# SD-101D_Robotics_Cape.net
KiCad netlist of a schematic drawn in EAGLE
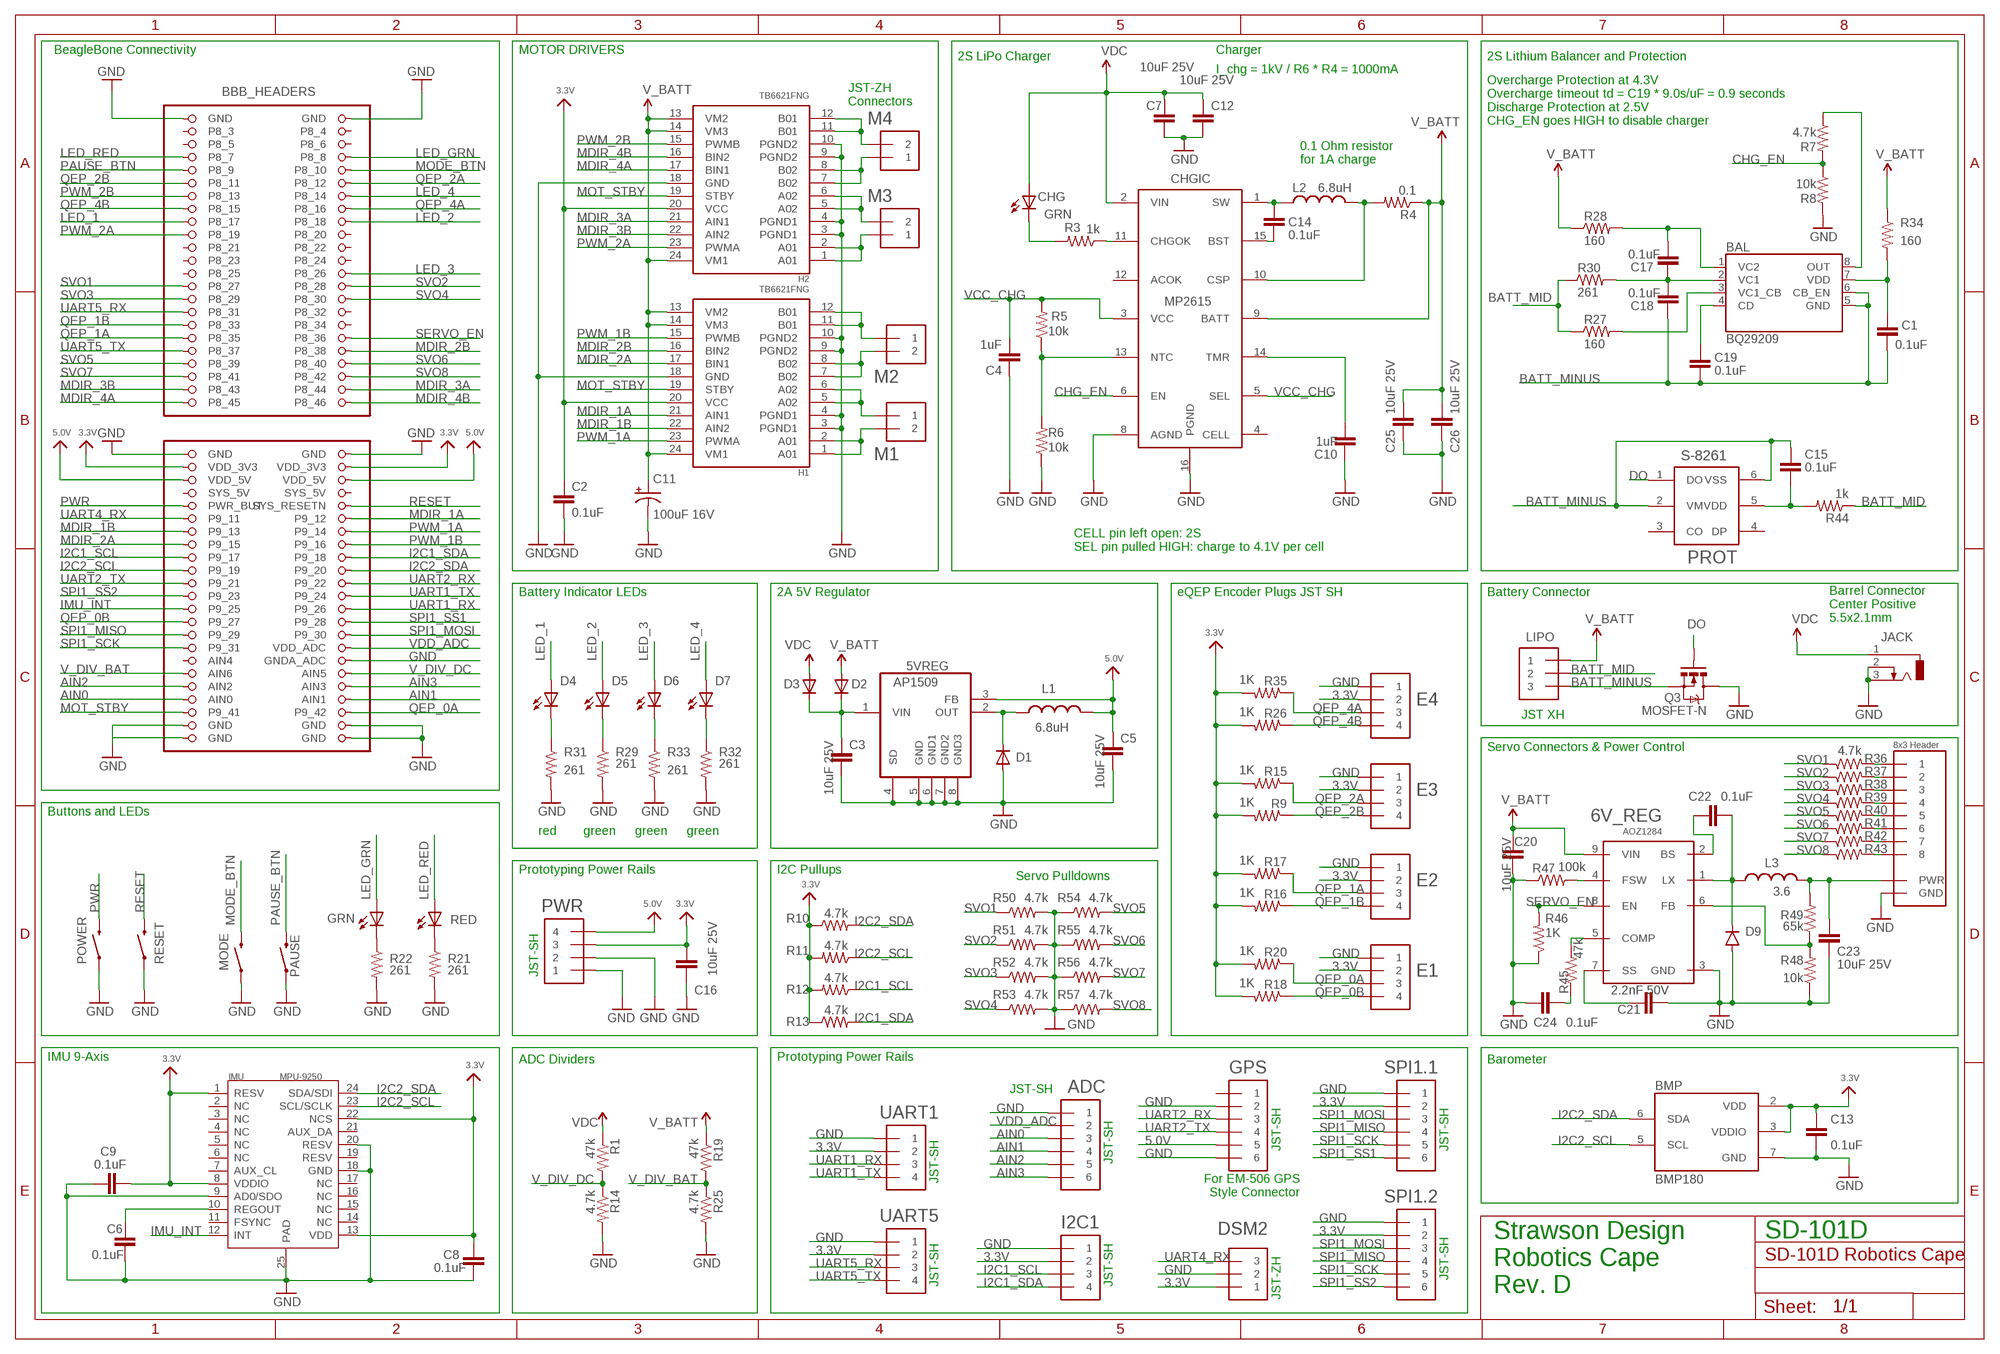
[diagram p0: schematic, sheet 1]

(export (version "E")
  (design (tool "Eeschema 10.0.6"))
  (components
    (comp (ref "5VREG")
      (value "AP1509SOIC-8-TIGHT")
      (footprint "eagle-import:SO08-TIGHT")
      (libsource (lib "eagle-import") (part "AP1509SOIC-8-TIGHT"))
    )
    (comp (ref "6V_REG")
      (value "AOZ1284")
      (footprint "eagle-import:SO08-EXPOSED")
      (libsource (lib "eagle-import") (part "AOZ1284"))
    )
    (comp (ref "ADC")
      (value "JST_SH_6")
      (footprint "eagle-import:JST_SH_6")
      (libsource (lib "eagle-import") (part "JST_SH_6"))
    )
    (comp (ref "BAL")
      (value "BQ29209")
      (footprint "eagle-import:8-SON_3X3MM")
      (libsource (lib "eagle-import") (part "BQ29209"))
    )
    (comp (ref "BBB_HEADERS")
      (value "BEAGLEBONE_OUTLINE")
      (footprint "eagle-import:BEAGLEBONE_SHIELD")
      (libsource (lib "eagle-import") (part "BEAGLEBONE_OUTLINE"))
    )
    (comp (ref "BMP")
      (value "BMP180")
      (footprint "eagle-import:BMP180")
      (libsource (lib "eagle-import") (part "BMP180"))
    )
    (comp (ref "C1")
      (value "0.1uF")
      (footprint "eagle-import:0402-CAP")
      (libsource (lib "eagle-import") (part "Strawson_Eagle_Lib_CAP0402-CAP"))
    )
    (comp (ref "C2")
      (value "0.1uF")
      (footprint "eagle-import:0402-CAP")
      (libsource (lib "eagle-import") (part "Strawson_Eagle_Lib_CAP0402-CAP"))
    )
    (comp (ref "C3")
      (value "10uF 25V")
      (footprint "eagle-import:0805")
      (libsource (lib "eagle-import") (part "CAP0805"))
    )
    (comp (ref "C4")
      (value "1uF")
      (footprint "eagle-import:0402-CAP")
      (libsource (lib "eagle-import") (part "Strawson_Eagle_Lib_CAP0402-CAP"))
    )
    (comp (ref "C5")
      (value "10uF 25V")
      (footprint "eagle-import:0805")
      (libsource (lib "eagle-import") (part "CAP0805"))
    )
    (comp (ref "C6")
      (value "0.1uF")
      (footprint "eagle-import:0402-CAP")
      (libsource (lib "eagle-import") (part "Strawson_Eagle_Lib_CAP0402-CAP"))
    )
    (comp (ref "C7")
      (value "10uF 25V")
      (footprint "eagle-import:0805")
      (libsource (lib "eagle-import") (part "CAP0805"))
    )
    (comp (ref "C8")
      (value "0.1uF")
      (footprint "eagle-import:0402-CAP")
      (libsource (lib "eagle-import") (part "Strawson_Eagle_Lib_CAP0402-CAP"))
    )
    (comp (ref "C9")
      (value "0.1uF")
      (footprint "eagle-import:0402-CAP")
      (libsource (lib "eagle-import") (part "Strawson_Eagle_Lib_CAP0402-CAP"))
    )
    (comp (ref "C10")
      (value "1uF")
      (footprint "eagle-import:0402-CAP")
      (libsource (lib "eagle-import") (part "Strawson_Eagle_Lib_CAP0402-CAP"))
    )
    (comp (ref "C11")
      (value "100uF 16V")
      (footprint "eagle-import:PANASONIC_D")
      (libsource (lib "eagle-import") (part "CPOL-USD"))
    )
    (comp (ref "C12")
      (value "10uF 25V")
      (footprint "eagle-import:0805")
      (libsource (lib "eagle-import") (part "CAP0805"))
    )
    (comp (ref "C13")
      (value "0.1uF")
      (footprint "eagle-import:0402-CAP")
      (libsource (lib "eagle-import") (part "Strawson_Eagle_Lib_CAP0402-CAP"))
    )
    (comp (ref "C14")
      (value "0.1uF")
      (footprint "eagle-import:0402-CAP")
      (libsource (lib "eagle-import") (part "Strawson_Eagle_Lib_CAP0402-CAP"))
    )
    (comp (ref "C15")
      (value "0.1uF")
      (footprint "eagle-import:0402-CAP")
      (libsource (lib "eagle-import") (part "Strawson_Eagle_Lib_CAP0402-CAP"))
    )
    (comp (ref "C16")
      (value "10uF 25V")
      (footprint "eagle-import:0805")
      (libsource (lib "eagle-import") (part "CAP0805"))
    )
    (comp (ref "C17")
      (value "0.1uF")
      (footprint "eagle-import:0402-CAP")
      (libsource (lib "eagle-import") (part "Strawson_Eagle_Lib_CAP0402-CAP"))
    )
    (comp (ref "C18")
      (value "0.1uF")
      (footprint "eagle-import:0402-CAP")
      (libsource (lib "eagle-import") (part "Strawson_Eagle_Lib_CAP0402-CAP"))
    )
    (comp (ref "C19")
      (value "0.1uF")
      (footprint "eagle-import:0402-CAP")
      (libsource (lib "eagle-import") (part "Strawson_Eagle_Lib_CAP0402-CAP"))
    )
    (comp (ref "C20")
      (value "10uF 25V")
      (footprint "eagle-import:0805")
      (libsource (lib "eagle-import") (part "CAP0805"))
    )
    (comp (ref "C21")
      (value "2.2nF 50V")
      (footprint "eagle-import:0402-CAP")
      (libsource (lib "eagle-import") (part "Strawson_Eagle_Lib_CAP0402-CAP"))
    )
    (comp (ref "C22")
      (value "0.1uF")
      (footprint "eagle-import:0402-CAP")
      (libsource (lib "eagle-import") (part "Strawson_Eagle_Lib_CAP0402-CAP"))
    )
    (comp (ref "C23")
      (value "10uF 25V")
      (footprint "eagle-import:0805")
      (libsource (lib "eagle-import") (part "CAP0805"))
    )
    (comp (ref "C24")
      (value "0.1uF")
      (footprint "eagle-import:0402-CAP")
      (libsource (lib "eagle-import") (part "Strawson_Eagle_Lib_CAP0402-CAP"))
    )
    (comp (ref "C25")
      (value "10uF 25V")
      (footprint "eagle-import:0805")
      (libsource (lib "eagle-import") (part "CAP0805"))
    )
    (comp (ref "C26")
      (value "10uF 25V")
      (footprint "eagle-import:0805")
      (libsource (lib "eagle-import") (part "CAP0805"))
    )
    (comp (ref "CHG")
      (value "GRN")
      (footprint "eagle-import:LED-0603")
      (libsource (lib "eagle-import") (part "LED0603"))
    )
    (comp (ref "CHGIC")
      (value "MP2615")
      (footprint "eagle-import:MP2615")
      (libsource (lib "eagle-import") (part "MP2615"))
    )
    (comp (ref "D1")
      (value "DIODESOD-123")
      (footprint "eagle-import:SOD-123")
      (libsource (lib "eagle-import") (part "DIODESOD-123"))
    )
    (comp (ref "D2")
      (value "DIODESOD-123")
      (footprint "eagle-import:SOD-123")
      (libsource (lib "eagle-import") (part "DIODESOD-123"))
    )
    (comp (ref "D3")
      (value "DIODESOD-123")
      (footprint "eagle-import:SOD-123")
      (libsource (lib "eagle-import") (part "DIODESOD-123"))
    )
    (comp (ref "D4")
      (value "RED")
      (footprint "eagle-import:LED-0603")
      (libsource (lib "eagle-import") (part "LED0603"))
    )
    (comp (ref "D5")
      (value "GREEN")
      (footprint "eagle-import:LED-0603")
      (libsource (lib "eagle-import") (part "LED0603"))
    )
    (comp (ref "D6")
      (value "GREEN")
      (footprint "eagle-import:LED-0603")
      (libsource (lib "eagle-import") (part "LED0603"))
    )
    (comp (ref "D7")
      (value "GREEN")
      (footprint "eagle-import:LED-0603")
      (libsource (lib "eagle-import") (part "LED0603"))
    )
    (comp (ref "D9")
      (value "DIODEDO214AA")
      (footprint "eagle-import:DO-214AA")
      (libsource (lib "eagle-import") (part "DIODEDO214AA"))
    )
    (comp (ref "DSM2")
      (value "JST_ZH_3")
      (footprint "eagle-import:JST_ZH_3")
      (libsource (lib "eagle-import") (part "JST_ZH_3"))
    )
    (comp (ref "E1")
      (value "JST_SH_4")
      (footprint "eagle-import:JST_SH_4_SMD")
      (libsource (lib "eagle-import") (part "JST_SH_4"))
    )
    (comp (ref "E2")
      (value "JST_SH_4")
      (footprint "eagle-import:JST_SH_4_SMD")
      (libsource (lib "eagle-import") (part "JST_SH_4"))
    )
    (comp (ref "E3")
      (value "JST_SH_4")
      (footprint "eagle-import:JST_SH_4_SMD")
      (libsource (lib "eagle-import") (part "JST_SH_4"))
    )
    (comp (ref "E4")
      (value "JST_SH_4")
      (footprint "eagle-import:JST_SH_4_SMD")
      (libsource (lib "eagle-import") (part "JST_SH_4"))
    )
    (comp (ref "GPS")
      (value "JST_SH_6")
      (footprint "eagle-import:JST_SH_6")
      (libsource (lib "eagle-import") (part "JST_SH_6"))
    )
    (comp (ref "GRN")
      (value "GRN")
      (footprint "eagle-import:LED-0603")
      (libsource (lib "eagle-import") (part "LED0603"))
    )
    (comp (ref "H1")
      (value "TB6621FNG")
      (footprint "eagle-import:SSOP24")
      (libsource (lib "eagle-import") (part "TB6621FNG"))
    )
    (comp (ref "H2")
      (value "TB6621FNG")
      (footprint "eagle-import:SSOP24")
      (libsource (lib "eagle-import") (part "TB6621FNG"))
    )
    (comp (ref "I2C1")
      (value "JST_SH_4")
      (footprint "eagle-import:JST_SH_4_SMD")
      (libsource (lib "eagle-import") (part "JST_SH_4"))
    )
    (comp (ref "IMU")
      (value "MPU-9250")
      (footprint "eagle-import:QFN24G-0.4-3X3MM")
      (libsource (lib "eagle-import") (part "MPU-9250"))
    )
    (comp (ref "JACK")
      (value "5.5x2.1mm")
      (footprint "eagle-import:DCJ0303")
      (libsource (lib "eagle-import") (part "DCJ0303"))
    )
    (comp (ref "L1")
      (value "6.8uH")
      (footprint "eagle-import:SRN6045")
      (libsource (lib "eagle-import") (part "INDUCTORBOURNS_SRN6045"))
    )
    (comp (ref "L2")
      (value "6.8uH")
      (footprint "eagle-import:SRN6045")
      (libsource (lib "eagle-import") (part "INDUCTORBOURNS_SRN6045"))
    )
    (comp (ref "L3")
      (value "3.6")
      (footprint "eagle-import:8X8MM_INDUCTOR")
      (libsource (lib "eagle-import") (part "INDUCTOR"))
    )
    (comp (ref "LIPO")
      (value "JST_XH_3-PIN")
      (footprint "eagle-import:JST_XH_3-PIN")
      (libsource (lib "eagle-import") (part "JST_XH_3-PIN"))
    )
    (comp (ref "M1")
      (value "JST_ZH_2")
      (footprint "eagle-import:JST_ZH_2")
      (libsource (lib "eagle-import") (part "JST_ZH_2"))
    )
    (comp (ref "M2")
      (value "JST_ZH_2")
      (footprint "eagle-import:JST_ZH_2")
      (libsource (lib "eagle-import") (part "JST_ZH_2"))
    )
    (comp (ref "M3")
      (value "JST_ZH_2")
      (footprint "eagle-import:JST_ZH_2")
      (libsource (lib "eagle-import") (part "JST_ZH_2"))
    )
    (comp (ref "M4")
      (value "JST_ZH_2")
      (footprint "eagle-import:JST_ZH_2")
      (libsource (lib "eagle-import") (part "JST_ZH_2"))
    )
    (comp (ref "MODE")
      (value "SWITCH-MOMENTARY-2-SMD-1101NE")
      (footprint "eagle-import:TACTILE-SWITCH-1101NE")
      (libsource (lib "eagle-import") (part "SWITCH-MOMENTARY-2-SMD-1101NE"))
    )
    (comp (ref "PAUSE")
      (value "SWITCH-MOMENTARY-2-SMD-1101NE")
      (footprint "eagle-import:TACTILE-SWITCH-1101NE")
      (libsource (lib "eagle-import") (part "SWITCH-MOMENTARY-2-SMD-1101NE"))
    )
    (comp (ref "POWER")
      (value "SWITCH-MOMENTARY-2-SMD-1101NE")
      (footprint "eagle-import:TACTILE-SWITCH-1101NE")
      (libsource (lib "eagle-import") (part "SWITCH-MOMENTARY-2-SMD-1101NE"))
    )
    (comp (ref "PROT")
      (value "S-8261")
      (footprint "eagle-import:SOT-236")
      (libsource (lib "eagle-import") (part "S-8261"))
    )
    (comp (ref "PWR")
      (value "JST_SH_4")
      (footprint "eagle-import:JST_SH_4_SMD")
      (libsource (lib "eagle-import") (part "JST_SH_4"))
    )
    (comp (ref "Q3")
      (value "MOSFET-N")
      (footprint "eagle-import:SO08-TIGHT")
      (libsource (lib "eagle-import") (part "MOSFET-NCHANNEL"))
    )
    (comp (ref "R1")
      (value "47k")
      (footprint "eagle-import:0402-RES")
      (libsource (lib "eagle-import") (part "RESISTOR0402-RES"))
    )
    (comp (ref "R3")
      (value "1k")
      (footprint "eagle-import:0402-RES")
      (libsource (lib "eagle-import") (part "RESISTOR0402-RES"))
    )
    (comp (ref "R4")
      (value "0.1")
      (footprint "eagle-import:0603-RES")
      (libsource (lib "eagle-import") (part "RESISTOR0603"))
    )
    (comp (ref "R5")
      (value "10k")
      (footprint "eagle-import:0402-RES")
      (libsource (lib "eagle-import") (part "RESISTOR0402-RES"))
    )
    (comp (ref "R6")
      (value "10k")
      (footprint "eagle-import:0402-RES")
      (libsource (lib "eagle-import") (part "RESISTOR0402-RES"))
    )
    (comp (ref "R7")
      (value "4.7k")
      (footprint "eagle-import:0402-RES")
      (libsource (lib "eagle-import") (part "RESISTOR0402-RES"))
    )
    (comp (ref "R8")
      (value "10k")
      (footprint "eagle-import:0402-RES")
      (libsource (lib "eagle-import") (part "RESISTOR0402-RES"))
    )
    (comp (ref "R9")
      (value "1K")
      (footprint "eagle-import:0402-RES")
      (libsource (lib "eagle-import") (part "RESISTOR0402-RES"))
    )
    (comp (ref "R10")
      (value "4.7k")
      (footprint "eagle-import:0402-RES")
      (libsource (lib "eagle-import") (part "RESISTOR0402-RES"))
    )
    (comp (ref "R11")
      (value "4.7k")
      (footprint "eagle-import:0402-RES")
      (libsource (lib "eagle-import") (part "RESISTOR0402-RES"))
    )
    (comp (ref "R12")
      (value "4.7k")
      (footprint "eagle-import:0402-RES")
      (libsource (lib "eagle-import") (part "RESISTOR0402-RES"))
    )
    (comp (ref "R13")
      (value "4.7k")
      (footprint "eagle-import:0402-RES")
      (libsource (lib "eagle-import") (part "RESISTOR0402-RES"))
    )
    (comp (ref "R14")
      (value "4.7k")
      (footprint "eagle-import:0402-RES")
      (libsource (lib "eagle-import") (part "RESISTOR0402-RES"))
    )
    (comp (ref "R15")
      (value "1K")
      (footprint "eagle-import:0402-RES")
      (libsource (lib "eagle-import") (part "RESISTOR0402-RES"))
    )
    (comp (ref "R16")
      (value "1K")
      (footprint "eagle-import:0402-RES")
      (libsource (lib "eagle-import") (part "RESISTOR0402-RES"))
    )
    (comp (ref "R17")
      (value "1K")
      (footprint "eagle-import:0402-RES")
      (libsource (lib "eagle-import") (part "RESISTOR0402-RES"))
    )
    (comp (ref "R18")
      (value "1K")
      (footprint "eagle-import:0402-RES")
      (libsource (lib "eagle-import") (part "RESISTOR0402-RES"))
    )
    (comp (ref "R19")
      (value "47k")
      (footprint "eagle-import:0402-RES")
      (libsource (lib "eagle-import") (part "RESISTOR0402-RES"))
    )
    (comp (ref "R20")
      (value "1K")
      (footprint "eagle-import:0402-RES")
      (libsource (lib "eagle-import") (part "RESISTOR0402-RES"))
    )
    (comp (ref "R21")
      (value "261")
      (footprint "eagle-import:0402-RES")
      (libsource (lib "eagle-import") (part "RESISTOR0402-RES"))
    )
    (comp (ref "R22")
      (value "261")
      (footprint "eagle-import:0402-RES")
      (libsource (lib "eagle-import") (part "RESISTOR0402-RES"))
    )
    (comp (ref "R25")
      (value "4.7k")
      (footprint "eagle-import:0402-RES")
      (libsource (lib "eagle-import") (part "RESISTOR0402-RES"))
    )
    (comp (ref "R26")
      (value "1K")
      (footprint "eagle-import:0402-RES")
      (libsource (lib "eagle-import") (part "RESISTOR0402-RES"))
    )
    (comp (ref "R27")
      (value "160")
      (footprint "eagle-import:0402-RES")
      (libsource (lib "eagle-import") (part "RESISTOR0402-RES"))
    )
    (comp (ref "R28")
      (value "160")
      (footprint "eagle-import:0402-RES")
      (libsource (lib "eagle-import") (part "RESISTOR0402-RES"))
    )
    (comp (ref "R29")
      (value "261")
      (footprint "eagle-import:0402-RES")
      (libsource (lib "eagle-import") (part "RESISTOR0402-RES"))
    )
    (comp (ref "R30")
      (value "261")
      (footprint "eagle-import:0402-RES")
      (libsource (lib "eagle-import") (part "RESISTOR0402-RES"))
    )
    (comp (ref "R31")
      (value "261")
      (footprint "eagle-import:0402-RES")
      (libsource (lib "eagle-import") (part "RESISTOR0402-RES"))
    )
    (comp (ref "R32")
      (value "261")
      (footprint "eagle-import:0402-RES")
      (libsource (lib "eagle-import") (part "RESISTOR0402-RES"))
    )
    (comp (ref "R33")
      (value "261")
      (footprint "eagle-import:0402-RES")
      (libsource (lib "eagle-import") (part "RESISTOR0402-RES"))
    )
    (comp (ref "R34")
      (value "160")
      (footprint "eagle-import:0402-RES")
      (libsource (lib "eagle-import") (part "RESISTOR0402-RES"))
    )
    (comp (ref "R35")
      (value "1K")
      (footprint "eagle-import:0402-RES")
      (libsource (lib "eagle-import") (part "RESISTOR0402-RES"))
    )
    (comp (ref "R36")
      (value "4.7k")
      (footprint "eagle-import:0402-RES")
      (libsource (lib "eagle-import") (part "RESISTOR0402-RES"))
    )
    (comp (ref "R37")
      (value "4.7k")
      (footprint "eagle-import:0402-RES")
      (libsource (lib "eagle-import") (part "RESISTOR0402-RES"))
    )
    (comp (ref "R38")
      (value "4.7k")
      (footprint "eagle-import:0402-RES")
      (libsource (lib "eagle-import") (part "RESISTOR0402-RES"))
    )
    (comp (ref "R39")
      (value "4.7k")
      (footprint "eagle-import:0402-RES")
      (libsource (lib "eagle-import") (part "RESISTOR0402-RES"))
    )
    (comp (ref "R40")
      (value "4.7k")
      (footprint "eagle-import:0402-RES")
      (libsource (lib "eagle-import") (part "RESISTOR0402-RES"))
    )
    (comp (ref "R41")
      (value "4.7k")
      (footprint "eagle-import:0402-RES")
      (libsource (lib "eagle-import") (part "RESISTOR0402-RES"))
    )
    (comp (ref "R42")
      (value "4.7k")
      (footprint "eagle-import:0402-RES")
      (libsource (lib "eagle-import") (part "RESISTOR0402-RES"))
    )
    (comp (ref "R43")
      (value "4.7k")
      (footprint "eagle-import:0402-RES")
      (libsource (lib "eagle-import") (part "RESISTOR0402-RES"))
    )
    (comp (ref "R44")
      (value "1k")
      (footprint "eagle-import:0402-RES")
      (libsource (lib "eagle-import") (part "RESISTOR0402-RES"))
    )
    (comp (ref "R45")
      (value "47k")
      (footprint "eagle-import:0402-RES")
      (libsource (lib "eagle-import") (part "RESISTOR0402-RES"))
    )
    (comp (ref "R46")
      (value "1K")
      (footprint "eagle-import:0402-RES")
      (libsource (lib "eagle-import") (part "RESISTOR0402-RES"))
    )
    (comp (ref "R47")
      (value "100k")
      (footprint "eagle-import:0402-RES")
      (libsource (lib "eagle-import") (part "RESISTOR0402-RES"))
    )
    (comp (ref "R48")
      (value "10k")
      (footprint "eagle-import:0402-RES")
      (libsource (lib "eagle-import") (part "RESISTOR0402-RES"))
    )
    (comp (ref "R49")
      (value "65k")
      (footprint "eagle-import:0402-RES")
      (libsource (lib "eagle-import") (part "RESISTOR0402-RES"))
    )
    (comp (ref "R50")
      (value "4.7k")
      (footprint "eagle-import:0402-RES")
      (libsource (lib "eagle-import") (part "RESISTOR0402-RES"))
    )
    (comp (ref "R51")
      (value "4.7k")
      (footprint "eagle-import:0402-RES")
      (libsource (lib "eagle-import") (part "RESISTOR0402-RES"))
    )
    (comp (ref "R52")
      (value "4.7k")
      (footprint "eagle-import:0402-RES")
      (libsource (lib "eagle-import") (part "RESISTOR0402-RES"))
    )
    (comp (ref "R53")
      (value "4.7k")
      (footprint "eagle-import:0402-RES")
      (libsource (lib "eagle-import") (part "RESISTOR0402-RES"))
    )
    (comp (ref "R54")
      (value "4.7k")
      (footprint "eagle-import:0402-RES")
      (libsource (lib "eagle-import") (part "RESISTOR0402-RES"))
    )
    (comp (ref "R55")
      (value "4.7k")
      (footprint "eagle-import:0402-RES")
      (libsource (lib "eagle-import") (part "RESISTOR0402-RES"))
    )
    (comp (ref "R56")
      (value "4.7k")
      (footprint "eagle-import:0402-RES")
      (libsource (lib "eagle-import") (part "RESISTOR0402-RES"))
    )
    (comp (ref "R57")
      (value "4.7k")
      (footprint "eagle-import:0402-RES")
      (libsource (lib "eagle-import") (part "RESISTOR0402-RES"))
    )
    (comp (ref "RED")
      (value "RED")
      (footprint "eagle-import:LED-0603")
      (libsource (lib "eagle-import") (part "LED0603"))
    )
    (comp (ref "RESET")
      (value "SWITCH-MOMENTARY-2-SMD-1101NE")
      (footprint "eagle-import:TACTILE-SWITCH-1101NE")
      (libsource (lib "eagle-import") (part "SWITCH-MOMENTARY-2-SMD-1101NE"))
    )
    (comp (ref "SPI1.1")
      (value "JST_SH_6")
      (footprint "eagle-import:JST_SH_6")
      (libsource (lib "eagle-import") (part "JST_SH_6"))
    )
    (comp (ref "SPI1.2")
      (value "JST_SH_6")
      (footprint "eagle-import:JST_SH_6")
      (libsource (lib "eagle-import") (part "JST_SH_6"))
    )
    (comp (ref "U$1")
      (value "SERVO_HEADERS_8X")
      (footprint "eagle-import:3X8_0.1__HEADER")
      (libsource (lib "eagle-import") (part "SERVO_HEADERS_8X"))
    )
    (comp (ref "UART1")
      (value "JST_SH_4")
      (footprint "eagle-import:JST_SH_4_SMD")
      (libsource (lib "eagle-import") (part "JST_SH_4"))
    )
    (comp (ref "UART5")
      (value "JST_SH_4")
      (footprint "eagle-import:JST_SH_4_SMD")
      (libsource (lib "eagle-import") (part "JST_SH_4"))
    )
  )
  (nets
    (net (code "1") (name "/AIN0") (class "Default")
      (node (ref "ADC") (pin "3") (pinfunction "3_3") (pintype "bidirectional"))
      (node (ref "BBB_HEADERS") (pin "85") (pinfunction "AIN0_85") (pintype "power_in"))
    )
    (net (code "2") (name "/AIN1") (class "Default")
      (node (ref "ADC") (pin "4") (pinfunction "4_4") (pintype "bidirectional"))
      (node (ref "BBB_HEADERS") (pin "86") (pinfunction "AIN1_86") (pintype "passive"))
    )
    (net (code "3") (name "/AIN2") (class "Default")
      (node (ref "ADC") (pin "5") (pinfunction "5_5") (pintype "bidirectional"))
      (node (ref "BBB_HEADERS") (pin "83") (pinfunction "AIN2_83") (pintype "passive"))
    )
    (net (code "4") (name "/AIN3") (class "Default")
      (node (ref "ADC") (pin "6") (pinfunction "6_6") (pintype "bidirectional"))
      (node (ref "BBB_HEADERS") (pin "84") (pinfunction "AIN3_84") (pintype "passive"))
    )
    (net (code "5") (name "/BATT_MID") (class "Default")
      (node (ref "LIPO") (pin "P$2") (pinfunction "2_P$2") (pintype "passive"))
      (node (ref "R27") (pin "1") (pinfunction "1_1") (pintype "passive"))
      (node (ref "R30") (pin "1") (pinfunction "1_1") (pintype "passive"))
      (node (ref "R44") (pin "1") (pinfunction "1_1") (pintype "passive"))
    )
    (net (code "6") (name "/BATT_MINUS") (class "Default")
      (node (ref "BAL") (pin "5") (pinfunction "GND_5") (pintype "bidirectional"))
      (node (ref "BAL") (pin "6") (pinfunction "CB_EN_6") (pintype "bidirectional"))
      (node (ref "C1") (pin "2") (pinfunction "2_2") (pintype "passive"))
      (node (ref "C15") (pin "1") (pinfunction "1_1") (pintype "passive"))
      (node (ref "C18") (pin "1") (pinfunction "1_1") (pintype "passive"))
      (node (ref "C19") (pin "2") (pinfunction "2_2") (pintype "passive"))
      (node (ref "LIPO") (pin "P$3") (pinfunction "3_P$3") (pintype "passive"))
      (node (ref "PROT") (pin "2") (pinfunction "VM_2") (pintype "bidirectional"))
      (node (ref "PROT") (pin "6") (pinfunction "VSS_6") (pintype "bidirectional"))
      (node (ref "Q3") (pin "1") (pinfunction "S_1") (pintype "passive"))
      (node (ref "Q3") (pin "2") (pinfunction "S_2") (pintype "passive"))
      (node (ref "Q3") (pin "3") (pinfunction "S_3") (pintype "passive"))
    )
    (net (code "7") (name "/CHG_EN") (class "Default")
      (node (ref "CHGIC") (pin "6") (pinfunction "EN_6") (pintype "bidirectional"))
      (node (ref "R7") (pin "2") (pinfunction "2_2") (pintype "passive"))
      (node (ref "R8") (pin "1") (pinfunction "1_1") (pintype "passive"))
    )
    (net (code "8") (name "/DO") (class "Default")
      (node (ref "PROT") (pin "1") (pinfunction "DO_1") (pintype "bidirectional"))
      (node (ref "Q3") (pin "4") (pinfunction "G_4") (pintype "passive"))
    )
    (net (code "9") (name "/I2C1_SCL") (class "Default")
      (node (ref "BBB_HEADERS") (pin "63") (pinfunction "P9_17_63") (pintype "passive"))
      (node (ref "I2C1") (pin "3") (pinfunction "3_3") (pintype "bidirectional"))
      (node (ref "R12") (pin "1") (pinfunction "1_1") (pintype "passive"))
    )
    (net (code "10") (name "/I2C1_SDA") (class "Default")
      (node (ref "BBB_HEADERS") (pin "64") (pinfunction "P9_18_64") (pintype "passive"))
      (node (ref "I2C1") (pin "4") (pinfunction "4_4") (pintype "bidirectional"))
      (node (ref "R13") (pin "2") (pinfunction "2_2") (pintype "passive"))
    )
    (net (code "11") (name "/I2C2_SCL") (class "Default")
      (node (ref "BBB_HEADERS") (pin "65") (pinfunction "P9_19_65") (pintype "passive"))
      (node (ref "BMP") (pin "5") (pinfunction "SCL_5") (pintype "input"))
      (node (ref "IMU") (pin "23") (pinfunction "SCL/SCLK_23") (pintype "bidirectional"))
      (node (ref "R11") (pin "1") (pinfunction "1_1") (pintype "passive"))
    )
    (net (code "12") (name "/I2C2_SDA") (class "Default")
      (node (ref "BBB_HEADERS") (pin "66") (pinfunction "P9_20_66") (pintype "passive"))
      (node (ref "BMP") (pin "6") (pinfunction "SDA_6") (pintype "bidirectional"))
      (node (ref "IMU") (pin "24") (pinfunction "SDA/SDI_24") (pintype "bidirectional"))
      (node (ref "R10") (pin "2") (pinfunction "2_2") (pintype "passive"))
    )
    (net (code "13") (name "/IMU_INT") (class "Default")
      (node (ref "BBB_HEADERS") (pin "71") (pinfunction "P9_25_71") (pintype "passive"))
      (node (ref "IMU") (pin "12") (pinfunction "INT_12") (pintype "bidirectional"))
    )
    (net (code "14") (name "/LED_1") (class "Default")
      (node (ref "BBB_HEADERS") (pin "17") (pinfunction "P8_17_17") (pintype "passive"))
      (node (ref "D4") (pin "A") (pinfunction "A_A") (pintype "passive"))
    )
    (net (code "15") (name "/LED_2") (class "Default")
      (node (ref "BBB_HEADERS") (pin "18") (pinfunction "P8_18_18") (pintype "passive"))
      (node (ref "D5") (pin "A") (pinfunction "A_A") (pintype "passive"))
    )
    (net (code "16") (name "/LED_3") (class "Default")
      (node (ref "BBB_HEADERS") (pin "26") (pinfunction "P8_26_26") (pintype "passive"))
      (node (ref "D6") (pin "A") (pinfunction "A_A") (pintype "passive"))
    )
    (net (code "17") (name "/LED_4") (class "Default")
      (node (ref "BBB_HEADERS") (pin "14") (pinfunction "P8_14_14") (pintype "passive"))
      (node (ref "D7") (pin "A") (pinfunction "A_A") (pintype "passive"))
    )
    (net (code "18") (name "/LED_GRN") (class "Default")
      (node (ref "BBB_HEADERS") (pin "8") (pinfunction "P8_8_8") (pintype "passive"))
      (node (ref "GRN") (pin "A") (pinfunction "A_A") (pintype "passive"))
    )
    (net (code "19") (name "/LED_RED") (class "Default")
      (node (ref "BBB_HEADERS") (pin "7") (pinfunction "P8_7_7") (pintype "passive"))
      (node (ref "RED") (pin "A") (pinfunction "A_A") (pintype "passive"))
    )
    (net (code "20") (name "/MDIR_1A") (class "Default")
      (node (ref "BBB_HEADERS") (pin "58") (pinfunction "P9_12_58") (pintype "passive"))
      (node (ref "H1") (pin "21") (pinfunction "AIN1_21") (pintype "bidirectional"))
    )
    (net (code "21") (name "/MDIR_1B") (class "Default")
      (node (ref "BBB_HEADERS") (pin "59") (pinfunction "P9_13_59") (pintype "passive"))
      (node (ref "H1") (pin "22") (pinfunction "AIN2_22") (pintype "bidirectional"))
    )
    (net (code "22") (name "/MDIR_2A") (class "Default")
      (node (ref "BBB_HEADERS") (pin "61") (pinfunction "P9_15_61") (pintype "passive"))
      (node (ref "H1") (pin "17") (pinfunction "BIN1_17") (pintype "bidirectional"))
    )
    (net (code "23") (name "/MDIR_2B") (class "Default")
      (node (ref "BBB_HEADERS") (pin "38") (pinfunction "P8_38_38") (pintype "passive"))
      (node (ref "H1") (pin "16") (pinfunction "BIN2_16") (pintype "bidirectional"))
    )
    (net (code "24") (name "/MDIR_3A") (class "Default")
      (node (ref "BBB_HEADERS") (pin "44") (pinfunction "P8_44_44") (pintype "passive"))
      (node (ref "H2") (pin "21") (pinfunction "AIN1_21") (pintype "bidirectional"))
    )
    (net (code "25") (name "/MDIR_3B") (class "Default")
      (node (ref "BBB_HEADERS") (pin "43") (pinfunction "P8_43_43") (pintype "passive"))
      (node (ref "H2") (pin "22") (pinfunction "AIN2_22") (pintype "bidirectional"))
    )
    (net (code "26") (name "/MDIR_4A") (class "Default")
      (node (ref "BBB_HEADERS") (pin "45") (pinfunction "P8_45_45") (pintype "passive"))
      (node (ref "H2") (pin "17") (pinfunction "BIN1_17") (pintype "bidirectional"))
    )
    (net (code "27") (name "/MDIR_4B") (class "Default")
      (node (ref "BBB_HEADERS") (pin "46") (pinfunction "P8_46_46") (pintype "passive"))
      (node (ref "H2") (pin "16") (pinfunction "BIN2_16") (pintype "bidirectional"))
    )
    (net (code "28") (name "/MODE_BTN") (class "Default")
      (node (ref "BBB_HEADERS") (pin "10") (pinfunction "P8_10_10") (pintype "passive"))
      (node (ref "MODE") (pin "P$2") (pinfunction "2_P$2") (pintype "passive"))
    )
    (net (code "29") (name "/MOT_STBY") (class "Default")
      (node (ref "BBB_HEADERS") (pin "87") (pinfunction "P9_41_87") (pintype "input"))
      (node (ref "H1") (pin "19") (pinfunction "STBY_19") (pintype "bidirectional"))
      (node (ref "H2") (pin "19") (pinfunction "STBY_19") (pintype "bidirectional"))
    )
    (net (code "30") (name "/PAUSE_BTN") (class "Default")
      (node (ref "BBB_HEADERS") (pin "9") (pinfunction "P8_9_9") (pintype "passive"))
      (node (ref "PAUSE") (pin "P$2") (pinfunction "2_P$2") (pintype "passive"))
    )
    (net (code "31") (name "/PWM_1A") (class "Default")
      (node (ref "BBB_HEADERS") (pin "60") (pinfunction "P9_14_60") (pintype "passive"))
      (node (ref "H1") (pin "23") (pinfunction "PWMA_23") (pintype "bidirectional"))
    )
    (net (code "32") (name "/PWM_1B") (class "Default")
      (node (ref "BBB_HEADERS") (pin "62") (pinfunction "P9_16_62") (pintype "passive"))
      (node (ref "H1") (pin "15") (pinfunction "PWMB_15") (pintype "bidirectional"))
    )
    (net (code "33") (name "/PWM_2A") (class "Default")
      (node (ref "BBB_HEADERS") (pin "19") (pinfunction "P8_19_19") (pintype "passive"))
      (node (ref "H2") (pin "23") (pinfunction "PWMA_23") (pintype "bidirectional"))
    )
    (net (code "34") (name "/PWM_2B") (class "Default")
      (node (ref "BBB_HEADERS") (pin "13") (pinfunction "P8_13_13") (pintype "passive"))
      (node (ref "H2") (pin "15") (pinfunction "PWMB_15") (pintype "bidirectional"))
    )
    (net (code "35") (name "/PWR") (class "Default")
      (node (ref "BBB_HEADERS") (pin "55") (pinfunction "PWR_BUT_55") (pintype "passive"))
      (node (ref "POWER") (pin "P$2") (pinfunction "2_P$2") (pintype "passive"))
    )
    (net (code "36") (name "/QEP_0A") (class "Default")
      (node (ref "BBB_HEADERS") (pin "88") (pinfunction "P9_42_88") (pintype "passive"))
      (node (ref "E1") (pin "3") (pinfunction "3_3") (pintype "bidirectional"))
      (node (ref "R20") (pin "1") (pinfunction "1_1") (pintype "passive"))
    )
    (net (code "37") (name "/QEP_0B") (class "Default")
      (node (ref "BBB_HEADERS") (pin "73") (pinfunction "P9_27_73") (pintype "passive"))
      (node (ref "E1") (pin "4") (pinfunction "4_4") (pintype "bidirectional"))
      (node (ref "R18") (pin "1") (pinfunction "1_1") (pintype "passive"))
    )
    (net (code "38") (name "/QEP_1A") (class "Default")
      (node (ref "BBB_HEADERS") (pin "35") (pinfunction "P8_35_35") (pintype "passive"))
      (node (ref "E2") (pin "3") (pinfunction "3_3") (pintype "bidirectional"))
      (node (ref "R17") (pin "1") (pinfunction "1_1") (pintype "passive"))
    )
    (net (code "39") (name "/QEP_1B") (class "Default")
      (node (ref "BBB_HEADERS") (pin "33") (pinfunction "P8_33_33") (pintype "passive"))
      (node (ref "E2") (pin "4") (pinfunction "4_4") (pintype "bidirectional"))
      (node (ref "R16") (pin "1") (pinfunction "1_1") (pintype "passive"))
    )
    (net (code "40") (name "/QEP_2A") (class "Default")
      (node (ref "BBB_HEADERS") (pin "12") (pinfunction "P8_12_12") (pintype "passive"))
      (node (ref "E3") (pin "3") (pinfunction "3_3") (pintype "bidirectional"))
      (node (ref "R15") (pin "1") (pinfunction "1_1") (pintype "passive"))
    )
    (net (code "41") (name "/QEP_2B") (class "Default")
      (node (ref "BBB_HEADERS") (pin "11") (pinfunction "P8_11_11") (pintype "passive"))
      (node (ref "E3") (pin "4") (pinfunction "4_4") (pintype "bidirectional"))
      (node (ref "R9") (pin "1") (pinfunction "1_1") (pintype "passive"))
    )
    (net (code "42") (name "/QEP_4A") (class "Default")
      (node (ref "BBB_HEADERS") (pin "16") (pinfunction "P8_16_16") (pintype "passive"))
      (node (ref "E4") (pin "3") (pinfunction "3_3") (pintype "bidirectional"))
      (node (ref "R35") (pin "1") (pinfunction "1_1") (pintype "passive"))
    )
    (net (code "43") (name "/QEP_4B") (class "Default")
      (node (ref "BBB_HEADERS") (pin "15") (pinfunction "P8_15_15") (pintype "passive"))
      (node (ref "E4") (pin "4") (pinfunction "4_4") (pintype "bidirectional"))
      (node (ref "R26") (pin "1") (pinfunction "1_1") (pintype "passive"))
    )
    (net (code "44") (name "/RESET") (class "Default")
      (node (ref "BBB_HEADERS") (pin "56") (pinfunction "SYS_RESETN_56") (pintype "passive"))
      (node (ref "RESET") (pin "P$2") (pinfunction "2_P$2") (pintype "passive"))
    )
    (net (code "45") (name "/SERVO_EN") (class "Default")
      (node (ref "6V_REG") (pin "8") (pinfunction "EN_8") (pintype "bidirectional"))
      (node (ref "BBB_HEADERS") (pin "36") (pinfunction "P8_36_36") (pintype "passive"))
      (node (ref "R46") (pin "2") (pinfunction "2_2") (pintype "passive"))
    )
    (net (code "46") (name "/SPI1_MISO") (class "Default")
      (node (ref "BBB_HEADERS") (pin "75") (pinfunction "P9_29_75") (pintype "passive"))
      (node (ref "SPI1.1") (pin "4") (pinfunction "4_4") (pintype "bidirectional"))
      (node (ref "SPI1.2") (pin "4") (pinfunction "4_4") (pintype "bidirectional"))
    )
    (net (code "47") (name "/SPI1_MOSI") (class "Default")
      (node (ref "BBB_HEADERS") (pin "76") (pinfunction "P9_30_76") (pintype "passive"))
      (node (ref "SPI1.1") (pin "3") (pinfunction "3_3") (pintype "bidirectional"))
      (node (ref "SPI1.2") (pin "3") (pinfunction "3_3") (pintype "bidirectional"))
    )
    (net (code "48") (name "/SPI1_SCK") (class "Default")
      (node (ref "BBB_HEADERS") (pin "77") (pinfunction "P9_31_77") (pintype "passive"))
      (node (ref "SPI1.1") (pin "5") (pinfunction "5_5") (pintype "bidirectional"))
      (node (ref "SPI1.2") (pin "5") (pinfunction "5_5") (pintype "bidirectional"))
    )
    (net (code "49") (name "/SPI1_SS1") (class "Default")
      (node (ref "BBB_HEADERS") (pin "74") (pinfunction "P9_28_74") (pintype "passive"))
      (node (ref "SPI1.1") (pin "6") (pinfunction "6_6") (pintype "bidirectional"))
    )
    (net (code "50") (name "/SPI1_SS2") (class "Default")
      (node (ref "BBB_HEADERS") (pin "69") (pinfunction "P9_23_69") (pintype "passive"))
      (node (ref "SPI1.2") (pin "6") (pinfunction "6_6") (pintype "bidirectional"))
    )
    (net (code "51") (name "/SVO1") (class "Default")
      (node (ref "BBB_HEADERS") (pin "27") (pinfunction "P8_27_27") (pintype "passive"))
      (node (ref "R36") (pin "1") (pinfunction "1_1") (pintype "passive"))
      (node (ref "R50") (pin "1") (pinfunction "1_1") (pintype "passive"))
    )
    (net (code "52") (name "/SVO2") (class "Default")
      (node (ref "BBB_HEADERS") (pin "28") (pinfunction "P8_28_28") (pintype "passive"))
      (node (ref "R37") (pin "1") (pinfunction "1_1") (pintype "passive"))
      (node (ref "R51") (pin "1") (pinfunction "1_1") (pintype "passive"))
    )
    (net (code "53") (name "/SVO3") (class "Default")
      (node (ref "BBB_HEADERS") (pin "29") (pinfunction "P8_29_29") (pintype "passive"))
      (node (ref "R38") (pin "1") (pinfunction "1_1") (pintype "passive"))
      (node (ref "R52") (pin "1") (pinfunction "1_1") (pintype "passive"))
    )
    (net (code "54") (name "/SVO4") (class "Default")
      (node (ref "BBB_HEADERS") (pin "30") (pinfunction "P8_30_30") (pintype "passive"))
      (node (ref "R39") (pin "1") (pinfunction "1_1") (pintype "passive"))
      (node (ref "R53") (pin "1") (pinfunction "1_1") (pintype "passive"))
    )
    (net (code "55") (name "/SVO5") (class "Default")
      (node (ref "BBB_HEADERS") (pin "39") (pinfunction "P8_39_39") (pintype "passive"))
      (node (ref "R40") (pin "1") (pinfunction "1_1") (pintype "passive"))
      (node (ref "R54") (pin "2") (pinfunction "2_2") (pintype "passive"))
    )
    (net (code "56") (name "/SVO6") (class "Default")
      (node (ref "BBB_HEADERS") (pin "40") (pinfunction "P8_40_40") (pintype "passive"))
      (node (ref "R41") (pin "1") (pinfunction "1_1") (pintype "passive"))
      (node (ref "R55") (pin "2") (pinfunction "2_2") (pintype "passive"))
    )
    (net (code "57") (name "/SVO7") (class "Default")
      (node (ref "BBB_HEADERS") (pin "41") (pinfunction "P8_41_41") (pintype "passive"))
      (node (ref "R42") (pin "1") (pinfunction "1_1") (pintype "passive"))
      (node (ref "R56") (pin "2") (pinfunction "2_2") (pintype "passive"))
    )
    (net (code "58") (name "/SVO8") (class "Default")
      (node (ref "BBB_HEADERS") (pin "42") (pinfunction "P8_42_42") (pintype "passive"))
      (node (ref "R43") (pin "1") (pinfunction "1_1") (pintype "passive"))
      (node (ref "R57") (pin "2") (pinfunction "2_2") (pintype "passive"))
    )
    (net (code "59") (name "/SYS_5V") (class "Default")
      (node (ref "BBB_HEADERS") (pin "53") (pinfunction "SYS_5V_53") (pintype "power_in"))
    )
    (net (code "60") (name "/UART1_RX") (class "Default")
      (node (ref "BBB_HEADERS") (pin "72") (pinfunction "P9_26_72") (pintype "passive"))
      (node (ref "UART1") (pin "3") (pinfunction "3_3") (pintype "bidirectional"))
    )
    (net (code "61") (name "/UART1_TX") (class "Default")
      (node (ref "BBB_HEADERS") (pin "70") (pinfunction "P9_24_70") (pintype "passive"))
      (node (ref "UART1") (pin "4") (pinfunction "4_4") (pintype "bidirectional"))
    )
    (net (code "62") (name "/UART2_RX") (class "Default")
      (node (ref "BBB_HEADERS") (pin "68") (pinfunction "P9_22_68") (pintype "passive"))
      (node (ref "GPS") (pin "3") (pinfunction "3_3") (pintype "bidirectional"))
    )
    (net (code "63") (name "/UART2_TX") (class "Default")
      (node (ref "BBB_HEADERS") (pin "67") (pinfunction "P9_21_67") (pintype "passive"))
      (node (ref "GPS") (pin "4") (pinfunction "4_4") (pintype "bidirectional"))
    )
    (net (code "64") (name "/UART4_RX") (class "Default")
      (node (ref "BBB_HEADERS") (pin "57") (pinfunction "P9_11_57") (pintype "passive"))
      (node (ref "DSM2") (pin "P$3") (pinfunction "3_P$3") (pintype "bidirectional"))
    )
    (net (code "65") (name "/UART5_RX") (class "Default")
      (node (ref "BBB_HEADERS") (pin "31") (pinfunction "P8_31_31") (pintype "passive"))
      (node (ref "UART5") (pin "3") (pinfunction "3_3") (pintype "bidirectional"))
    )
    (net (code "66") (name "/UART5_TX") (class "Default")
      (node (ref "BBB_HEADERS") (pin "37") (pinfunction "P8_37_37") (pintype "passive"))
      (node (ref "UART5") (pin "4") (pinfunction "4_4") (pintype "bidirectional"))
    )
    (net (code "67") (name "/VCC_CHG") (class "Default")
      (node (ref "C4") (pin "2") (pinfunction "2_2") (pintype "passive"))
      (node (ref "CHGIC") (pin "3") (pinfunction "VCC_3") (pintype "bidirectional"))
      (node (ref "CHGIC") (pin "5") (pinfunction "SEL_5") (pintype "bidirectional"))
      (node (ref "R5") (pin "2") (pinfunction "2_2") (pintype "passive"))
    )
    (net (code "68") (name "/VDD_ADC") (class "Default")
      (node (ref "ADC") (pin "2") (pinfunction "2_2") (pintype "bidirectional"))
      (node (ref "BBB_HEADERS") (pin "78") (pinfunction "VDD_ADC_78") (pintype "passive"))
    )
    (net (code "69") (name "/V_DIV_BAT") (class "Default")
      (node (ref "BBB_HEADERS") (pin "81") (pinfunction "AIN6_81") (pintype "passive"))
      (node (ref "R19") (pin "2") (pinfunction "2_2") (pintype "passive"))
      (node (ref "R25") (pin "1") (pinfunction "1_1") (pintype "passive"))
    )
    (net (code "70") (name "/V_DIV_DC") (class "Default")
      (node (ref "BBB_HEADERS") (pin "82") (pinfunction "AIN5_82") (pintype "passive"))
      (node (ref "R1") (pin "2") (pinfunction "2_2") (pintype "passive"))
      (node (ref "R14") (pin "1") (pinfunction "1_1") (pintype "passive"))
    )
    (net (code "71") (name "3.3V") (class "Default")
      (node (ref "BBB_HEADERS") (pin "49") (pinfunction "VDD_3V3_49") (pintype "power_in"))
      (node (ref "BBB_HEADERS") (pin "50") (pinfunction "VDD_3V3_50") (pintype "power_in"))
      (node (ref "BMP") (pin "2") (pinfunction "VDD_2") (pintype "power_in"))
      (node (ref "BMP") (pin "3") (pinfunction "VDDIO_3") (pintype "power_in"))
      (node (ref "C13") (pin "1") (pinfunction "1_1") (pintype "passive"))
      (node (ref "C16") (pin "1") (pinfunction "1_1") (pintype "passive"))
      (node (ref "C2") (pin "2") (pinfunction "2_2") (pintype "passive"))
      (node (ref "C8") (pin "1") (pinfunction "1_1") (pintype "passive"))
      (node (ref "C9") (pin "2") (pinfunction "2_2") (pintype "passive"))
      (node (ref "DSM2") (pin "P$1") (pinfunction "1_P$1") (pintype "bidirectional"))
      (node (ref "E1") (pin "2") (pinfunction "2_2") (pintype "bidirectional"))
      (node (ref "E2") (pin "2") (pinfunction "2_2") (pintype "bidirectional"))
      (node (ref "E3") (pin "2") (pinfunction "2_2") (pintype "bidirectional"))
      (node (ref "E4") (pin "2") (pinfunction "2_2") (pintype "bidirectional"))
      (node (ref "H1") (pin "20") (pinfunction "VCC_20") (pintype "bidirectional"))
      (node (ref "H2") (pin "20") (pinfunction "VCC_20") (pintype "bidirectional"))
      (node (ref "I2C1") (pin "2") (pinfunction "2_2") (pintype "bidirectional"))
      (node (ref "IMU") (pin "1") (pinfunction "RESV_1") (pintype "bidirectional"))
      (node (ref "IMU") (pin "13") (pinfunction "VDD_13") (pintype "bidirectional"))
      (node (ref "IMU") (pin "22") (pinfunction "NCS_22") (pintype "bidirectional"))
      (node (ref "IMU") (pin "8") (pinfunction "VDDIO_8") (pintype "bidirectional"))
      (node (ref "PWR") (pin "3") (pinfunction "3_3") (pintype "bidirectional"))
      (node (ref "R10") (pin "1") (pinfunction "1_1") (pintype "passive"))
      (node (ref "R11") (pin "2") (pinfunction "2_2") (pintype "passive"))
      (node (ref "R12") (pin "2") (pinfunction "2_2") (pintype "passive"))
      (node (ref "R13") (pin "1") (pinfunction "1_1") (pintype "passive"))
      (node (ref "R15") (pin "2") (pinfunction "2_2") (pintype "passive"))
      (node (ref "R16") (pin "2") (pinfunction "2_2") (pintype "passive"))
      (node (ref "R17") (pin "2") (pinfunction "2_2") (pintype "passive"))
      (node (ref "R18") (pin "2") (pinfunction "2_2") (pintype "passive"))
      (node (ref "R20") (pin "2") (pinfunction "2_2") (pintype "passive"))
      (node (ref "R26") (pin "2") (pinfunction "2_2") (pintype "passive"))
      (node (ref "R35") (pin "2") (pinfunction "2_2") (pintype "passive"))
      (node (ref "R9") (pin "2") (pinfunction "2_2") (pintype "passive"))
      (node (ref "SPI1.1") (pin "2") (pinfunction "2_2") (pintype "bidirectional"))
      (node (ref "SPI1.2") (pin "2") (pinfunction "2_2") (pintype "bidirectional"))
      (node (ref "UART1") (pin "2") (pinfunction "2_2") (pintype "bidirectional"))
      (node (ref "UART5") (pin "2") (pinfunction "2_2") (pintype "bidirectional"))
    )
    (net (code "72") (name "5.0V") (class "Default")
      (node (ref "5VREG") (pin "3") (pinfunction "FB_3") (pintype "output"))
      (node (ref "BBB_HEADERS") (pin "51") (pinfunction "VDD_5V_51") (pintype "power_in"))
      (node (ref "BBB_HEADERS") (pin "52") (pinfunction "VDD_5V_52") (pintype "power_in"))
      (node (ref "C5") (pin "1") (pinfunction "1_1") (pintype "passive"))
      (node (ref "GPS") (pin "5") (pinfunction "5_5") (pintype "bidirectional"))
      (node (ref "L1") (pin "2") (pinfunction "2_2") (pintype "passive"))
      (node (ref "PWR") (pin "4") (pinfunction "4_4") (pintype "bidirectional"))
    )
    (net (code "73") (name "GND") (class "Default")
      (node (ref "5VREG") (pin "4") (pinfunction "SD_4") (pintype "input"))
      (node (ref "5VREG") (pin "5") (pinfunction "GND_5") (pintype "power_in"))
      (node (ref "5VREG") (pin "6") (pinfunction "GND1_6") (pintype "input"))
      (node (ref "5VREG") (pin "7") (pinfunction "GND2_7") (pintype "passive"))
      (node (ref "5VREG") (pin "8") (pinfunction "GND3_8") (pintype "power_in"))
      (node (ref "6V_REG") (pin "3") (pinfunction "GND_3") (pintype "bidirectional"))
      (node (ref "ADC") (pin "1") (pinfunction "1_1") (pintype "bidirectional"))
      (node (ref "BBB_HEADERS") (pin "1") (pinfunction "GND_1") (pintype "power_in"))
      (node (ref "BBB_HEADERS") (pin "2") (pinfunction "GND_2") (pintype "power_in"))
      (node (ref "BBB_HEADERS") (pin "47") (pinfunction "GND_47") (pintype "power_in"))
      (node (ref "BBB_HEADERS") (pin "48") (pinfunction "GND_48") (pintype "power_in"))
      (node (ref "BBB_HEADERS") (pin "80") (pinfunction "GNDA_ADC_80") (pintype "passive"))
      (node (ref "BBB_HEADERS") (pin "89") (pinfunction "GND_89") (pintype "power_in"))
      (node (ref "BBB_HEADERS") (pin "90") (pinfunction "GND_90") (pintype "power_in"))
      (node (ref "BBB_HEADERS") (pin "91") (pinfunction "GND_91") (pintype "power_in"))
      (node (ref "BBB_HEADERS") (pin "92") (pinfunction "GND_92") (pintype "power_in"))
      (node (ref "BMP") (pin "7") (pinfunction "GND_7") (pintype "power_in"))
      (node (ref "C10") (pin "1") (pinfunction "1_1") (pintype "passive"))
      (node (ref "C11") (pin "-") (pinfunction "-_-") (pintype "passive"))
      (node (ref "C12") (pin "2") (pinfunction "2_2") (pintype "passive"))
      (node (ref "C13") (pin "2") (pinfunction "2_2") (pintype "passive"))
      (node (ref "C16") (pin "2") (pinfunction "2_2") (pintype "passive"))
      (node (ref "C2") (pin "1") (pinfunction "1_1") (pintype "passive"))
      (node (ref "C20") (pin "1") (pinfunction "1_1") (pintype "passive"))
      (node (ref "C21") (pin "1") (pinfunction "1_1") (pintype "passive"))
      (node (ref "C23") (pin "1") (pinfunction "1_1") (pintype "passive"))
      (node (ref "C24") (pin "1") (pinfunction "1_1") (pintype "passive"))
      (node (ref "C25") (pin "2") (pinfunction "2_2") (pintype "passive"))
      (node (ref "C26") (pin "2") (pinfunction "2_2") (pintype "passive"))
      (node (ref "C3") (pin "2") (pinfunction "2_2") (pintype "passive"))
      (node (ref "C4") (pin "1") (pinfunction "1_1") (pintype "passive"))
      (node (ref "C5") (pin "2") (pinfunction "2_2") (pintype "passive"))
      (node (ref "C6") (pin "2") (pinfunction "2_2") (pintype "passive"))
      (node (ref "C7") (pin "2") (pinfunction "2_2") (pintype "passive"))
      (node (ref "C8") (pin "2") (pinfunction "2_2") (pintype "passive"))
      (node (ref "C9") (pin "1") (pinfunction "1_1") (pintype "passive"))
      (node (ref "CHGIC") (pin "16") (pinfunction "PGND_16") (pintype "bidirectional"))
      (node (ref "CHGIC") (pin "8") (pinfunction "AGND_8") (pintype "bidirectional"))
      (node (ref "D1") (pin "A") (pinfunction "A_A") (pintype "passive"))
      (node (ref "D9") (pin "A") (pinfunction "A_A") (pintype "passive"))
      (node (ref "DSM2") (pin "P$2") (pinfunction "2_P$2") (pintype "bidirectional"))
      (node (ref "E1") (pin "1") (pinfunction "1_1") (pintype "bidirectional"))
      (node (ref "E2") (pin "1") (pinfunction "1_1") (pintype "bidirectional"))
      (node (ref "E3") (pin "1") (pinfunction "1_1") (pintype "bidirectional"))
      (node (ref "E4") (pin "1") (pinfunction "1_1") (pintype "bidirectional"))
      (node (ref "GPS") (pin "2") (pinfunction "2_2") (pintype "bidirectional"))
      (node (ref "GPS") (pin "6") (pinfunction "6_6") (pintype "bidirectional"))
      (node (ref "H1") (pin "10") (pinfunction "PGND2_10") (pintype "bidirectional"))
      (node (ref "H1") (pin "18") (pinfunction "GND_18") (pintype "bidirectional"))
      (node (ref "H1") (pin "3") (pinfunction "PGND1_3") (pintype "bidirectional"))
      (node (ref "H1") (pin "4") (pinfunction "PGND1_4") (pintype "bidirectional"))
      (node (ref "H1") (pin "9") (pinfunction "PGND2_9") (pintype "bidirectional"))
      (node (ref "H2") (pin "10") (pinfunction "PGND2_10") (pintype "bidirectional"))
      (node (ref "H2") (pin "18") (pinfunction "GND_18") (pintype "bidirectional"))
      (node (ref "H2") (pin "3") (pinfunction "PGND1_3") (pintype "bidirectional"))
      (node (ref "H2") (pin "4") (pinfunction "PGND1_4") (pintype "bidirectional"))
      (node (ref "H2") (pin "9") (pinfunction "PGND2_9") (pintype "bidirectional"))
      (node (ref "I2C1") (pin "1") (pinfunction "1_1") (pintype "bidirectional"))
      (node (ref "IMU") (pin "18") (pinfunction "GND_18") (pintype "bidirectional"))
      (node (ref "IMU") (pin "20") (pinfunction "RESV_20") (pintype "bidirectional"))
      (node (ref "IMU") (pin "25") (pinfunction "PAD_25") (pintype "bidirectional"))
      (node (ref "IMU") (pin "9") (pinfunction "AD0/SDO_9") (pintype "bidirectional"))
      (node (ref "JACK") (pin "2") (pinfunction "2_2") (pintype "passive"))
      (node (ref "JACK") (pin "3") (pinfunction "3_3") (pintype "passive"))
      (node (ref "MODE") (pin "P$1") (pinfunction "1_P$1") (pintype "passive"))
      (node (ref "PAUSE") (pin "P$1") (pinfunction "1_P$1") (pintype "passive"))
      (node (ref "POWER") (pin "P$1") (pinfunction "1_P$1") (pintype "passive"))
      (node (ref "PWR") (pin "1") (pinfunction "1_1") (pintype "bidirectional"))
      (node (ref "PWR") (pin "2") (pinfunction "2_2") (pintype "bidirectional"))
      (node (ref "Q3") (pin "5") (pinfunction "D_5") (pintype "passive"))
      (node (ref "Q3") (pin "6") (pinfunction "D_6") (pintype "passive"))
      (node (ref "Q3") (pin "7") (pinfunction "D_7") (pintype "passive"))
      (node (ref "Q3") (pin "8") (pinfunction "D_8") (pintype "passive"))
      (node (ref "R14") (pin "2") (pinfunction "2_2") (pintype "passive"))
      (node (ref "R21") (pin "2") (pinfunction "2_2") (pintype "passive"))
      (node (ref "R22") (pin "2") (pinfunction "2_2") (pintype "passive"))
      (node (ref "R25") (pin "2") (pinfunction "2_2") (pintype "passive"))
      (node (ref "R29") (pin "2") (pinfunction "2_2") (pintype "passive"))
      (node (ref "R31") (pin "2") (pinfunction "2_2") (pintype "passive"))
      (node (ref "R32") (pin "2") (pinfunction "2_2") (pintype "passive"))
      (node (ref "R33") (pin "2") (pinfunction "2_2") (pintype "passive"))
      (node (ref "R46") (pin "1") (pinfunction "1_1") (pintype "passive"))
      (node (ref "R47") (pin "1") (pinfunction "1_1") (pintype "passive"))
      (node (ref "R48") (pin "1") (pinfunction "1_1") (pintype "passive"))
      (node (ref "R50") (pin "2") (pinfunction "2_2") (pintype "passive"))
      (node (ref "R51") (pin "2") (pinfunction "2_2") (pintype "passive"))
      (node (ref "R52") (pin "2") (pinfunction "2_2") (pintype "passive"))
      (node (ref "R53") (pin "2") (pinfunction "2_2") (pintype "passive"))
      (node (ref "R54") (pin "1") (pinfunction "1_1") (pintype "passive"))
      (node (ref "R55") (pin "1") (pinfunction "1_1") (pintype "passive"))
      (node (ref "R56") (pin "1") (pinfunction "1_1") (pintype "passive"))
      (node (ref "R57") (pin "1") (pinfunction "1_1") (pintype "passive"))
      (node (ref "R6") (pin "1") (pinfunction "1_1") (pintype "passive"))
      (node (ref "R8") (pin "2") (pinfunction "2_2") (pintype "passive"))
      (node (ref "RESET") (pin "P$1") (pinfunction "1_P$1") (pintype "passive"))
      (node (ref "SPI1.1") (pin "1") (pinfunction "1_1") (pintype "bidirectional"))
      (node (ref "SPI1.2") (pin "1") (pinfunction "1_1") (pintype "bidirectional"))
      (node (ref "U$1") (pin "P$13") (pinfunction "GND_P$13") (pintype "bidirectional"))
      (node (ref "U$1") (pin "P$14") (pinfunction "GND_P$14") (pintype "bidirectional"))
      (node (ref "U$1") (pin "P$15") (pinfunction "GND_P$15") (pintype "bidirectional"))
      (node (ref "U$1") (pin "P$16") (pinfunction "GND_P$16") (pintype "bidirectional"))
      (node (ref "U$1") (pin "P$17") (pinfunction "GND_P$17") (pintype "bidirectional"))
      (node (ref "U$1") (pin "P$18") (pinfunction "GND_P$18") (pintype "bidirectional"))
      (node (ref "U$1") (pin "P$23") (pinfunction "GND_P$23") (pintype "bidirectional"))
      (node (ref "U$1") (pin "P$24") (pinfunction "GND_P$24") (pintype "bidirectional"))
      (node (ref "UART1") (pin "1") (pinfunction "1_1") (pintype "bidirectional"))
      (node (ref "UART5") (pin "1") (pinfunction "1_1") (pintype "bidirectional"))
    )
    (net (code "74") (name "Net-(5VREG-OUT)") (class "Default")
      (node (ref "5VREG") (pin "2") (pinfunction "OUT_2") (pintype "output"))
      (node (ref "D1") (pin "C") (pinfunction "C_C") (pintype "passive"))
      (node (ref "L1") (pin "1") (pinfunction "1_1") (pintype "passive"))
    )
    (net (code "75") (name "Net-(5VREG-VIN)") (class "Default")
      (node (ref "5VREG") (pin "1") (pinfunction "VIN_1") (pintype "input"))
      (node (ref "C3") (pin "1") (pinfunction "1_1") (pintype "passive"))
      (node (ref "D2") (pin "C") (pinfunction "C_C") (pintype "passive"))
      (node (ref "D3") (pin "C") (pinfunction "C_C") (pintype "passive"))
    )
    (net (code "76") (name "Net-(6V_REG-BS)") (class "Default")
      (node (ref "6V_REG") (pin "2") (pinfunction "BS_2") (pintype "bidirectional"))
      (node (ref "C22") (pin "1") (pinfunction "1_1") (pintype "passive"))
    )
    (net (code "77") (name "Net-(6V_REG-COMP)") (class "Default")
      (node (ref "6V_REG") (pin "5") (pinfunction "COMP_5") (pintype "bidirectional"))
      (node (ref "R45") (pin "2") (pinfunction "2_2") (pintype "passive"))
    )
    (net (code "78") (name "Net-(6V_REG-FB)") (class "Default")
      (node (ref "6V_REG") (pin "6") (pinfunction "FB_6") (pintype "bidirectional"))
      (node (ref "R48") (pin "2") (pinfunction "2_2") (pintype "passive"))
      (node (ref "R49") (pin "1") (pinfunction "1_1") (pintype "passive"))
    )
    (net (code "79") (name "Net-(6V_REG-FSW)") (class "Default")
      (node (ref "6V_REG") (pin "4") (pinfunction "FSW_4") (pintype "bidirectional"))
      (node (ref "R47") (pin "2") (pinfunction "2_2") (pintype "passive"))
    )
    (net (code "80") (name "Net-(6V_REG-LX)") (class "Default")
      (node (ref "6V_REG") (pin "1") (pinfunction "LX_1") (pintype "bidirectional"))
      (node (ref "C22") (pin "2") (pinfunction "2_2") (pintype "passive"))
      (node (ref "D9") (pin "C") (pinfunction "C_C") (pintype "passive"))
      (node (ref "L3") (pin "1") (pinfunction "1_1") (pintype "passive"))
    )
    (net (code "81") (name "Net-(6V_REG-SS)") (class "Default")
      (node (ref "6V_REG") (pin "7") (pinfunction "SS_7") (pintype "bidirectional"))
      (node (ref "C21") (pin "2") (pinfunction "2_2") (pintype "passive"))
    )
    (net (code "82") (name "Net-(BAL-CD)") (class "Default")
      (node (ref "BAL") (pin "4") (pinfunction "CD_4") (pintype "bidirectional"))
      (node (ref "C19") (pin "1") (pinfunction "1_1") (pintype "passive"))
    )
    (net (code "83") (name "Net-(BAL-OUT)") (class "Default")
      (node (ref "BAL") (pin "8") (pinfunction "OUT_8") (pintype "bidirectional"))
      (node (ref "R7") (pin "1") (pinfunction "1_1") (pintype "passive"))
    )
    (net (code "84") (name "Net-(BAL-VC1)") (class "Default")
      (node (ref "BAL") (pin "2") (pinfunction "VC1_2") (pintype "bidirectional"))
      (node (ref "C17") (pin "1") (pinfunction "1_1") (pintype "passive"))
      (node (ref "C18") (pin "2") (pinfunction "2_2") (pintype "passive"))
      (node (ref "R30") (pin "2") (pinfunction "2_2") (pintype "passive"))
    )
    (net (code "85") (name "Net-(BAL-VC1_CB)") (class "Default")
      (node (ref "BAL") (pin "3") (pinfunction "VC1_CB_3") (pintype "bidirectional"))
      (node (ref "R27") (pin "2") (pinfunction "2_2") (pintype "passive"))
    )
    (net (code "86") (name "Net-(BAL-VC2)") (class "Default")
      (node (ref "BAL") (pin "1") (pinfunction "VC2_1") (pintype "bidirectional"))
      (node (ref "C17") (pin "2") (pinfunction "2_2") (pintype "passive"))
      (node (ref "R28") (pin "2") (pinfunction "2_2") (pintype "passive"))
    )
    (net (code "87") (name "Net-(BAL-VDD)") (class "Default")
      (node (ref "BAL") (pin "7") (pinfunction "VDD_7") (pintype "bidirectional"))
      (node (ref "C1") (pin "1") (pinfunction "1_1") (pintype "passive"))
      (node (ref "R34") (pin "2") (pinfunction "2_2") (pintype "passive"))
    )
    (net (code "88") (name "Net-(C23-Pad2)") (class "Default")
      (node (ref "C23") (pin "2") (pinfunction "2_2") (pintype "passive"))
      (node (ref "L3") (pin "2") (pinfunction "2_2") (pintype "passive"))
      (node (ref "R49") (pin "2") (pinfunction "2_2") (pintype "passive"))
      (node (ref "U$1") (pin "P$10") (pinfunction "PWR_P$10") (pintype "bidirectional"))
      (node (ref "U$1") (pin "P$11") (pinfunction "PWR_P$11") (pintype "bidirectional"))
      (node (ref "U$1") (pin "P$12") (pinfunction "PWR_P$12") (pintype "bidirectional"))
      (node (ref "U$1") (pin "P$21") (pinfunction "PWR_P$21") (pintype "bidirectional"))
      (node (ref "U$1") (pin "P$22") (pinfunction "PWR_P$22") (pintype "bidirectional"))
      (node (ref "U$1") (pin "P$7") (pinfunction "PWR_P$7") (pintype "bidirectional"))
      (node (ref "U$1") (pin "P$8") (pinfunction "PWR_P$8") (pintype "bidirectional"))
      (node (ref "U$1") (pin "P$9") (pinfunction "PWR_P$9") (pintype "bidirectional"))
    )
    (net (code "89") (name "Net-(C24-Pad2)") (class "Default")
      (node (ref "C24") (pin "2") (pinfunction "2_2") (pintype "passive"))
      (node (ref "R45") (pin "1") (pinfunction "1_1") (pintype "passive"))
    )
    (net (code "90") (name "Net-(CHG-PadC)") (class "Default")
      (node (ref "CHG") (pin "C") (pinfunction "C_C") (pintype "passive"))
      (node (ref "R3") (pin "2") (pinfunction "2_2") (pintype "passive"))
    )
    (net (code "91") (name "Net-(CHGIC-BST)") (class "Default")
      (node (ref "C14") (pin "1") (pinfunction "1_1") (pintype "passive"))
      (node (ref "CHGIC") (pin "15") (pinfunction "BST_15") (pintype "bidirectional"))
    )
    (net (code "92") (name "Net-(CHGIC-CHGOK)") (class "Default")
      (node (ref "CHGIC") (pin "11") (pinfunction "CHGOK_11") (pintype "bidirectional"))
      (node (ref "R3") (pin "1") (pinfunction "1_1") (pintype "passive"))
    )
    (net (code "93") (name "Net-(CHGIC-CSP)") (class "Default")
      (node (ref "CHGIC") (pin "10") (pinfunction "CSP_10") (pintype "bidirectional"))
      (node (ref "L2") (pin "2") (pinfunction "2_2") (pintype "passive"))
      (node (ref "R4") (pin "2") (pinfunction "2_2") (pintype "passive"))
    )
    (net (code "94") (name "Net-(CHGIC-NTC)") (class "Default")
      (node (ref "CHGIC") (pin "13") (pinfunction "NTC_13") (pintype "bidirectional"))
      (node (ref "R5") (pin "1") (pinfunction "1_1") (pintype "passive"))
      (node (ref "R6") (pin "2") (pinfunction "2_2") (pintype "passive"))
    )
    (net (code "95") (name "Net-(CHGIC-SW)") (class "Default")
      (node (ref "C14") (pin "2") (pinfunction "2_2") (pintype "passive"))
      (node (ref "CHGIC") (pin "1") (pinfunction "SW_1") (pintype "bidirectional"))
      (node (ref "L2") (pin "1") (pinfunction "1_1") (pintype "passive"))
    )
    (net (code "96") (name "Net-(CHGIC-TMR)") (class "Default")
      (node (ref "C10") (pin "2") (pinfunction "2_2") (pintype "passive"))
      (node (ref "CHGIC") (pin "14") (pinfunction "TMR_14") (pintype "bidirectional"))
    )
    (net (code "97") (name "Net-(D4-PadC)") (class "Default")
      (node (ref "D4") (pin "C") (pinfunction "C_C") (pintype "passive"))
      (node (ref "R31") (pin "1") (pinfunction "1_1") (pintype "passive"))
    )
    (net (code "98") (name "Net-(D5-PadC)") (class "Default")
      (node (ref "D5") (pin "C") (pinfunction "C_C") (pintype "passive"))
      (node (ref "R29") (pin "1") (pinfunction "1_1") (pintype "passive"))
    )
    (net (code "99") (name "Net-(D6-PadC)") (class "Default")
      (node (ref "D6") (pin "C") (pinfunction "C_C") (pintype "passive"))
      (node (ref "R33") (pin "1") (pinfunction "1_1") (pintype "passive"))
    )
    (net (code "100") (name "Net-(D7-PadC)") (class "Default")
      (node (ref "D7") (pin "C") (pinfunction "C_C") (pintype "passive"))
      (node (ref "R32") (pin "1") (pinfunction "1_1") (pintype "passive"))
    )
    (net (code "101") (name "Net-(GRN-PadC)") (class "Default")
      (node (ref "GRN") (pin "C") (pinfunction "C_C") (pintype "passive"))
      (node (ref "R22") (pin "1") (pinfunction "1_1") (pintype "passive"))
    )
    (net (code "102") (name "Net-(IMU-REGOUT)") (class "Default")
      (node (ref "C6") (pin "1") (pinfunction "1_1") (pintype "passive"))
      (node (ref "IMU") (pin "10") (pinfunction "REGOUT_10") (pintype "bidirectional"))
    )
    (net (code "103") (name "Net-(M1-1)") (class "Default")
      (node (ref "H1") (pin "5") (pinfunction "A02_5") (pintype "bidirectional"))
      (node (ref "H1") (pin "6") (pinfunction "A02_6") (pintype "bidirectional"))
      (node (ref "M1") (pin "P$1") (pinfunction "1_P$1") (pintype "bidirectional"))
    )
    (net (code "104") (name "Net-(M1-2)") (class "Default")
      (node (ref "H1") (pin "1") (pinfunction "A01_1") (pintype "bidirectional"))
      (node (ref "H1") (pin "2") (pinfunction "A01_2") (pintype "bidirectional"))
      (node (ref "M1") (pin "P$2") (pinfunction "2_P$2") (pintype "bidirectional"))
    )
    (net (code "105") (name "Net-(M2-1)") (class "Default")
      (node (ref "H1") (pin "11") (pinfunction "B01_11") (pintype "bidirectional"))
      (node (ref "H1") (pin "12") (pinfunction "B01_12") (pintype "bidirectional"))
      (node (ref "M2") (pin "P$1") (pinfunction "1_P$1") (pintype "bidirectional"))
    )
    (net (code "106") (name "Net-(M2-2)") (class "Default")
      (node (ref "H1") (pin "7") (pinfunction "B02_7") (pintype "bidirectional"))
      (node (ref "H1") (pin "8") (pinfunction "B02_8") (pintype "bidirectional"))
      (node (ref "M2") (pin "P$2") (pinfunction "2_P$2") (pintype "bidirectional"))
    )
    (net (code "107") (name "Net-(M3-1)") (class "Default")
      (node (ref "H2") (pin "1") (pinfunction "A01_1") (pintype "bidirectional"))
      (node (ref "H2") (pin "2") (pinfunction "A01_2") (pintype "bidirectional"))
      (node (ref "M3") (pin "P$1") (pinfunction "1_P$1") (pintype "bidirectional"))
    )
    (net (code "108") (name "Net-(M3-2)") (class "Default")
      (node (ref "H2") (pin "5") (pinfunction "A02_5") (pintype "bidirectional"))
      (node (ref "H2") (pin "6") (pinfunction "A02_6") (pintype "bidirectional"))
      (node (ref "M3") (pin "P$2") (pinfunction "2_P$2") (pintype "bidirectional"))
    )
    (net (code "109") (name "Net-(M4-1)") (class "Default")
      (node (ref "H2") (pin "7") (pinfunction "B02_7") (pintype "bidirectional"))
      (node (ref "H2") (pin "8") (pinfunction "B02_8") (pintype "bidirectional"))
      (node (ref "M4") (pin "P$1") (pinfunction "1_P$1") (pintype "bidirectional"))
    )
    (net (code "110") (name "Net-(M4-2)") (class "Default")
      (node (ref "H2") (pin "11") (pinfunction "B01_11") (pintype "bidirectional"))
      (node (ref "H2") (pin "12") (pinfunction "B01_12") (pintype "bidirectional"))
      (node (ref "M4") (pin "P$2") (pinfunction "2_P$2") (pintype "bidirectional"))
    )
    (net (code "111") (name "Net-(PROT-VDD)") (class "Default")
      (node (ref "C15") (pin "2") (pinfunction "2_2") (pintype "passive"))
      (node (ref "PROT") (pin "5") (pinfunction "VDD_5") (pintype "bidirectional"))
      (node (ref "R44") (pin "2") (pinfunction "2_2") (pintype "passive"))
    )
    (net (code "112") (name "Net-(R21-Pad1)") (class "Default")
      (node (ref "R21") (pin "1") (pinfunction "1_1") (pintype "passive"))
      (node (ref "RED") (pin "C") (pinfunction "C_C") (pintype "passive"))
    )
    (net (code "113") (name "Net-(U$1-1)") (class "Default")
      (node (ref "R36") (pin "2") (pinfunction "2_2") (pintype "passive"))
      (node (ref "U$1") (pin "P$1") (pinfunction "1_P$1") (pintype "bidirectional"))
    )
    (net (code "114") (name "Net-(U$1-2)") (class "Default")
      (node (ref "R37") (pin "2") (pinfunction "2_2") (pintype "passive"))
      (node (ref "U$1") (pin "P$2") (pinfunction "2_P$2") (pintype "bidirectional"))
    )
    (net (code "115") (name "Net-(U$1-3)") (class "Default")
      (node (ref "R38") (pin "2") (pinfunction "2_2") (pintype "passive"))
      (node (ref "U$1") (pin "P$3") (pinfunction "3_P$3") (pintype "bidirectional"))
    )
    (net (code "116") (name "Net-(U$1-4)") (class "Default")
      (node (ref "R39") (pin "2") (pinfunction "2_2") (pintype "passive"))
      (node (ref "U$1") (pin "P$4") (pinfunction "4_P$4") (pintype "bidirectional"))
    )
    (net (code "117") (name "Net-(U$1-5)") (class "Default")
      (node (ref "R40") (pin "2") (pinfunction "2_2") (pintype "passive"))
      (node (ref "U$1") (pin "P$5") (pinfunction "5_P$5") (pintype "bidirectional"))
    )
    (net (code "118") (name "Net-(U$1-6)") (class "Default")
      (node (ref "R41") (pin "2") (pinfunction "2_2") (pintype "passive"))
      (node (ref "U$1") (pin "P$6") (pinfunction "6_P$6") (pintype "bidirectional"))
    )
    (net (code "119") (name "Net-(U$1-7)") (class "Default")
      (node (ref "R42") (pin "2") (pinfunction "2_2") (pintype "passive"))
      (node (ref "U$1") (pin "P$19") (pinfunction "7_P$19") (pintype "bidirectional"))
    )
    (net (code "120") (name "Net-(U$1-8)") (class "Default")
      (node (ref "R43") (pin "2") (pinfunction "2_2") (pintype "passive"))
      (node (ref "U$1") (pin "P$20") (pinfunction "8_P$20") (pintype "bidirectional"))
    )
    (net (code "121") (name "VDC") (class "Default")
      (node (ref "C12") (pin "1") (pinfunction "1_1") (pintype "passive"))
      (node (ref "C7") (pin "1") (pinfunction "1_1") (pintype "passive"))
      (node (ref "CHG") (pin "A") (pinfunction "A_A") (pintype "passive"))
      (node (ref "CHGIC") (pin "2") (pinfunction "VIN_2") (pintype "bidirectional"))
      (node (ref "D3") (pin "A") (pinfunction "A_A") (pintype "passive"))
      (node (ref "JACK") (pin "1") (pinfunction "1_1") (pintype "passive"))
      (node (ref "R1") (pin "1") (pinfunction "1_1") (pintype "passive"))
    )
    (net (code "122") (name "V_BATT") (class "Default")
      (node (ref "6V_REG") (pin "9") (pinfunction "VIN_9") (pintype "bidirectional"))
      (node (ref "C11") (pin "+") (pinfunction "+_+") (pintype "passive"))
      (node (ref "C20") (pin "2") (pinfunction "2_2") (pintype "passive"))
      (node (ref "C25") (pin "1") (pinfunction "1_1") (pintype "passive"))
      (node (ref "C26") (pin "1") (pinfunction "1_1") (pintype "passive"))
      (node (ref "CHGIC") (pin "9") (pinfunction "BATT_9") (pintype "bidirectional"))
      (node (ref "D2") (pin "A") (pinfunction "A_A") (pintype "passive"))
      (node (ref "H1") (pin "13") (pinfunction "VM2_13") (pintype "bidirectional"))
      (node (ref "H1") (pin "14") (pinfunction "VM3_14") (pintype "bidirectional"))
      (node (ref "H1") (pin "24") (pinfunction "VM1_24") (pintype "bidirectional"))
      (node (ref "H2") (pin "13") (pinfunction "VM2_13") (pintype "bidirectional"))
      (node (ref "H2") (pin "14") (pinfunction "VM3_14") (pintype "bidirectional"))
      (node (ref "H2") (pin "24") (pinfunction "VM1_24") (pintype "bidirectional"))
      (node (ref "LIPO") (pin "P$1") (pinfunction "1_P$1") (pintype "passive"))
      (node (ref "R19") (pin "1") (pinfunction "1_1") (pintype "passive"))
      (node (ref "R28") (pin "1") (pinfunction "1_1") (pintype "passive"))
      (node (ref "R34") (pin "1") (pinfunction "1_1") (pintype "passive"))
      (node (ref "R4") (pin "1") (pinfunction "1_1") (pintype "passive"))
    )
    (net (code "123") (name "unconnected-(BBB_HEADERS-AIN4-Pad79)") (class "Default")
      (node (ref "BBB_HEADERS") (pin "79") (pinfunction "AIN4_79") (pintype "passive"))
    )
    (net (code "124") (name "unconnected-(BBB_HEADERS-P8_3-Pad3)") (class "Default")
      (node (ref "BBB_HEADERS") (pin "3") (pinfunction "P8_3_3") (pintype "passive"))
    )
    (net (code "125") (name "unconnected-(BBB_HEADERS-P8_4-Pad4)") (class "Default")
      (node (ref "BBB_HEADERS") (pin "4") (pinfunction "P8_4_4") (pintype "passive"))
    )
    (net (code "126") (name "unconnected-(BBB_HEADERS-P8_5-Pad5)") (class "Default")
      (node (ref "BBB_HEADERS") (pin "5") (pinfunction "P8_5_5") (pintype "passive"))
    )
    (net (code "127") (name "unconnected-(BBB_HEADERS-P8_6-Pad6)") (class "Default")
      (node (ref "BBB_HEADERS") (pin "6") (pinfunction "P8_6_6") (pintype "passive"))
    )
    (net (code "128") (name "unconnected-(BBB_HEADERS-P8_20-Pad20)") (class "Default")
      (node (ref "BBB_HEADERS") (pin "20") (pinfunction "P8_20_20") (pintype "passive"))
    )
    (net (code "129") (name "unconnected-(BBB_HEADERS-P8_21-Pad21)") (class "Default")
      (node (ref "BBB_HEADERS") (pin "21") (pinfunction "P8_21_21") (pintype "passive"))
    )
    (net (code "130") (name "unconnected-(BBB_HEADERS-P8_22-Pad22)") (class "Default")
      (node (ref "BBB_HEADERS") (pin "22") (pinfunction "P8_22_22") (pintype "passive"))
    )
    (net (code "131") (name "unconnected-(BBB_HEADERS-P8_23-Pad23)") (class "Default")
      (node (ref "BBB_HEADERS") (pin "23") (pinfunction "P8_23_23") (pintype "passive"))
    )
    (net (code "132") (name "unconnected-(BBB_HEADERS-P8_24-Pad24)") (class "Default")
      (node (ref "BBB_HEADERS") (pin "24") (pinfunction "P8_24_24") (pintype "passive"))
    )
    (net (code "133") (name "unconnected-(BBB_HEADERS-P8_25-Pad25)") (class "Default")
      (node (ref "BBB_HEADERS") (pin "25") (pinfunction "P8_25_25") (pintype "passive"))
    )
    (net (code "134") (name "unconnected-(BBB_HEADERS-P8_32-Pad32)") (class "Default")
      (node (ref "BBB_HEADERS") (pin "32") (pinfunction "P8_32_32") (pintype "passive"))
    )
    (net (code "135") (name "unconnected-(BBB_HEADERS-P8_34-Pad34)") (class "Default")
      (node (ref "BBB_HEADERS") (pin "34") (pinfunction "P8_34_34") (pintype "passive"))
    )
    (net (code "136") (name "unconnected-(BBB_HEADERS-SYS_5V-Pad54)") (class "Default")
      (node (ref "BBB_HEADERS") (pin "54") (pinfunction "SYS_5V_54") (pintype "passive"))
    )
    (net (code "137") (name "unconnected-(CHGIC-ACOK-Pad12)") (class "Default")
      (node (ref "CHGIC") (pin "12") (pinfunction "ACOK_12") (pintype "bidirectional"))
    )
    (net (code "138") (name "unconnected-(CHGIC-CELL-Pad4)") (class "Default")
      (node (ref "CHGIC") (pin "4") (pinfunction "CELL_4") (pintype "bidirectional"))
    )
    (net (code "139") (name "unconnected-(GPS-Pad1)") (class "Default")
      (node (ref "GPS") (pin "1") (pinfunction "1_1") (pintype "bidirectional"))
    )
    (net (code "140") (name "unconnected-(IMU-AUX_CL-Pad7)") (class "Default")
      (node (ref "IMU") (pin "7") (pinfunction "AUX_CL_7") (pintype "bidirectional"))
    )
    (net (code "141") (name "unconnected-(IMU-AUX_DA-Pad21)") (class "Default")
      (node (ref "IMU") (pin "21") (pinfunction "AUX_DA_21") (pintype "bidirectional"))
    )
    (net (code "142") (name "unconnected-(IMU-FSYNC-Pad11)") (class "Default")
      (node (ref "IMU") (pin "11") (pinfunction "FSYNC_11") (pintype "bidirectional"))
    )
    (net (code "143") (name "unconnected-(IMU-NC-Pad2)") (class "Default")
      (node (ref "IMU") (pin "2") (pinfunction "NC_2") (pintype "bidirectional"))
    )
    (net (code "144") (name "unconnected-(IMU-NC-Pad3)") (class "Default")
      (node (ref "IMU") (pin "3") (pinfunction "NC_3") (pintype "bidirectional"))
    )
    (net (code "145") (name "unconnected-(IMU-NC-Pad4)") (class "Default")
      (node (ref "IMU") (pin "4") (pinfunction "NC_4") (pintype "bidirectional"))
    )
    (net (code "146") (name "unconnected-(IMU-NC-Pad5)") (class "Default")
      (node (ref "IMU") (pin "5") (pinfunction "NC_5") (pintype "bidirectional"))
    )
    (net (code "147") (name "unconnected-(IMU-NC-Pad6)") (class "Default")
      (node (ref "IMU") (pin "6") (pinfunction "NC_6") (pintype "bidirectional"))
    )
    (net (code "148") (name "unconnected-(IMU-NC-Pad14)") (class "Default")
      (node (ref "IMU") (pin "14") (pinfunction "NC_14") (pintype "bidirectional"))
    )
    (net (code "149") (name "unconnected-(IMU-NC-Pad15)") (class "Default")
      (node (ref "IMU") (pin "15") (pinfunction "NC_15") (pintype "bidirectional"))
    )
    (net (code "150") (name "unconnected-(IMU-NC-Pad16)") (class "Default")
      (node (ref "IMU") (pin "16") (pinfunction "NC_16") (pintype "bidirectional"))
    )
    (net (code "151") (name "unconnected-(IMU-NC-Pad17)") (class "Default")
      (node (ref "IMU") (pin "17") (pinfunction "NC_17") (pintype "bidirectional"))
    )
    (net (code "152") (name "unconnected-(IMU-RESV-Pad19)") (class "Default")
      (node (ref "IMU") (pin "19") (pinfunction "RESV_19") (pintype "bidirectional"))
    )
    (net (code "153") (name "unconnected-(PROT-CO-Pad3)") (class "Default")
      (node (ref "PROT") (pin "3") (pinfunction "CO_3") (pintype "bidirectional"))
    )
    (net (code "154") (name "unconnected-(PROT-DP-Pad4)") (class "Default")
      (node (ref "PROT") (pin "4") (pinfunction "DP_4") (pintype "bidirectional"))
    )
  )
)
